# coolrunner_bob.net
KiCad netlist of a schematic drawn in EAGLE
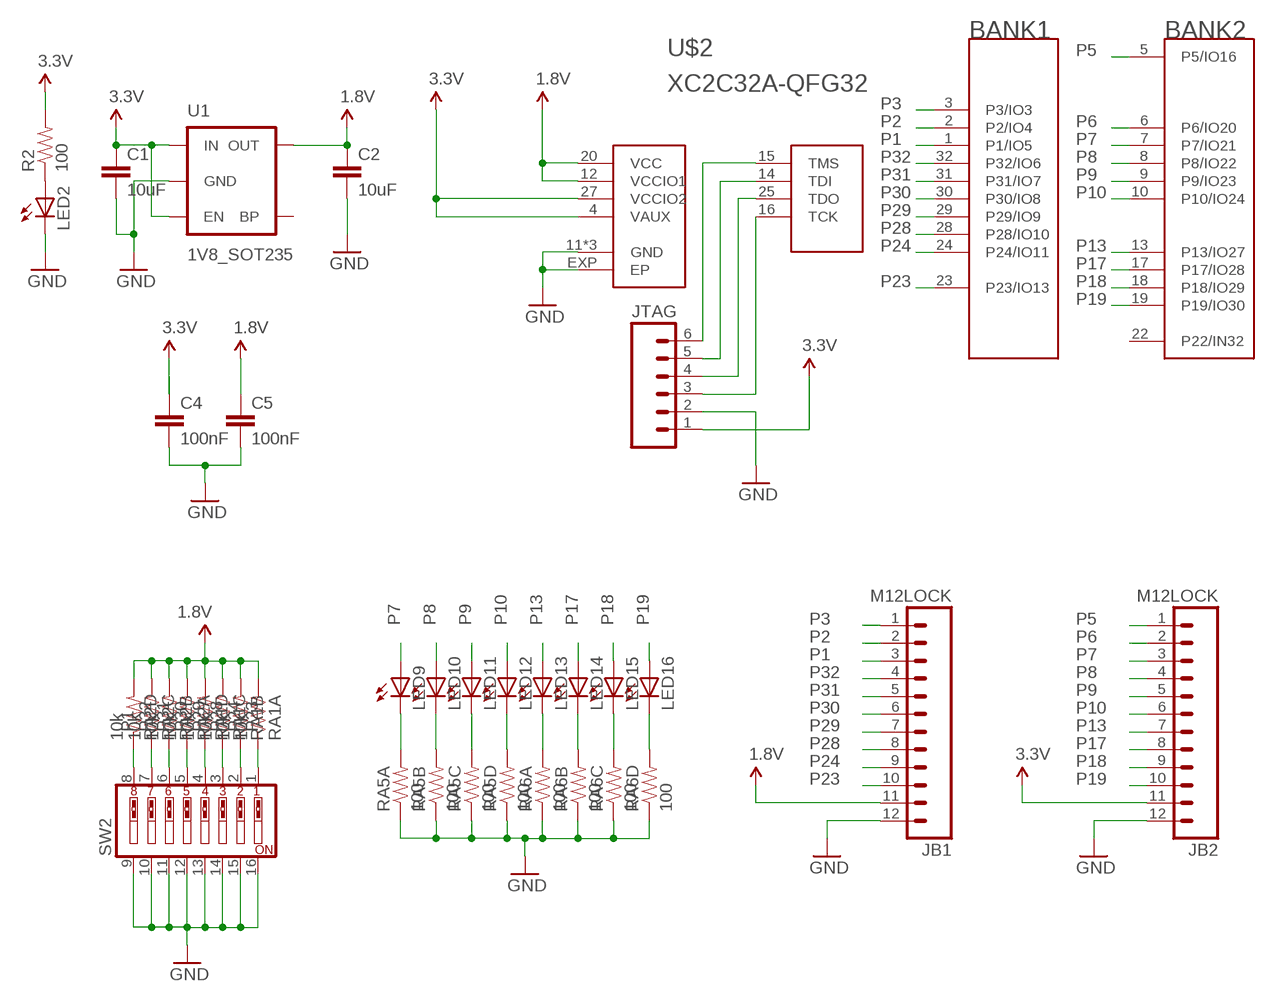
[diagram p0: schematic, sheet 1]

(export (version "E")
  (design (tool "Eeschema 10.0.6"))
  (components
    (comp (ref "C1")
      (value "10uF")
      (footprint "eagle-import:0805")
      (libsource (lib "eagle-import") (part "CAP0805"))
    )
    (comp (ref "C2")
      (value "10uF")
      (footprint "eagle-import:0805")
      (libsource (lib "eagle-import") (part "CAP0805"))
    )
    (comp (ref "C4")
      (value "100nF")
      (footprint "eagle-import:0402-CAP")
      (libsource (lib "eagle-import") (part "CAP0402-CAP"))
    )
    (comp (ref "C5")
      (value "100nF")
      (footprint "eagle-import:0402-CAP")
      (libsource (lib "eagle-import") (part "CAP0402-CAP"))
    )
    (comp (ref "JB1")
      (value "M12LOCK")
      (footprint "eagle-import:1X12_LOCK")
      (libsource (lib "eagle-import") (part "M12LOCK"))
    )
    (comp (ref "JB2")
      (value "M12LOCK")
      (footprint "eagle-import:1X12_LOCK")
      (libsource (lib "eagle-import") (part "M12LOCK"))
    )
    (comp (ref "JTAG")
      (value "M06LOCK")
      (footprint "eagle-import:1X06_LOCK")
      (libsource (lib "eagle-import") (part "M06LOCK"))
    )
    (comp (ref "LED2")
      (value "LED0603")
      (footprint "eagle-import:LED-0603")
      (libsource (lib "eagle-import") (part "LED0603"))
    )
    (comp (ref "LED9")
      (value "LED0603")
      (footprint "eagle-import:LED-0603")
      (libsource (lib "eagle-import") (part "LED0603"))
    )
    (comp (ref "LED10")
      (value "LED0603")
      (footprint "eagle-import:LED-0603")
      (libsource (lib "eagle-import") (part "LED0603"))
    )
    (comp (ref "LED11")
      (value "LED0603")
      (footprint "eagle-import:LED-0603")
      (libsource (lib "eagle-import") (part "LED0603"))
    )
    (comp (ref "LED12")
      (value "LED0603")
      (footprint "eagle-import:LED-0603")
      (libsource (lib "eagle-import") (part "LED0603"))
    )
    (comp (ref "LED13")
      (value "LED0603")
      (footprint "eagle-import:LED-0603")
      (libsource (lib "eagle-import") (part "LED0603"))
    )
    (comp (ref "LED14")
      (value "LED0603")
      (footprint "eagle-import:LED-0603")
      (libsource (lib "eagle-import") (part "LED0603"))
    )
    (comp (ref "LED15")
      (value "LED0603")
      (footprint "eagle-import:LED-0603")
      (libsource (lib "eagle-import") (part "LED0603"))
    )
    (comp (ref "LED16")
      (value "LED0603")
      (footprint "eagle-import:LED-0603")
      (libsource (lib "eagle-import") (part "LED0603"))
    )
    (comp (ref "R2")
      (value "100")
      (footprint "eagle-import:0603-RES")
      (libsource (lib "eagle-import") (part "RESISTOR0603-RES"))
    )
    (comp (ref "RA1")
      (value "10k")
      (footprint "eagle-import:0603-ARV")
      (libsource (lib "eagle-import") (part "RESISTOR_ARRAY0603_X4"))
    )
    (comp (ref "RA2")
      (value "10k")
      (footprint "eagle-import:0603-ARV")
      (libsource (lib "eagle-import") (part "RESISTOR_ARRAY0603_X4"))
    )
    (comp (ref "RA5")
      (value "100")
      (footprint "eagle-import:0603-ARV")
      (libsource (lib "eagle-import") (part "RESISTOR_ARRAY0603_X4"))
    )
    (comp (ref "RA6")
      (value "100")
      (footprint "eagle-import:0603-ARV")
      (libsource (lib "eagle-import") (part "RESISTOR_ARRAY0603_X4"))
    )
    (comp (ref "SW2")
      (value "SW_DIP-8")
      (footprint "eagle-import:DIPSWITCH-08")
      (libsource (lib "eagle-import") (part "SW_DIP-8"))
    )
    (comp (ref "U$2")
      (value "XC2C32A-QFG32")
      (footprint "eagle-import:QFN32-5X5")
      (libsource (lib "eagle-import") (part "XC2C32A-QFG32"))
    )
    (comp (ref "U1")
      (value "1V8_SOT235")
      (footprint "eagle-import:SOT23-5")
      (libsource (lib "eagle-import") (part "V_REG_LDOSMD"))
    )
  )
  (nets
    (net (code "1") (name "/P1") (class "Default")
      (node (ref "JB1") (pin "3") (pinfunction "3_3") (pintype "passive"))
      (node (ref "RA2") (pin "4") (pinfunction "1_4") (pintype "passive"))
      (node (ref "SW2") (pin "8") (pinfunction "8_8") (pintype "passive"))
      (node (ref "U$2") (pin "1") (pinfunction "P1/IO5_1") (pintype "bidirectional"))
    )
    (net (code "2") (name "/P2") (class "Default")
      (node (ref "JB1") (pin "2") (pinfunction "2_2") (pintype "passive"))
      (node (ref "U$2") (pin "2") (pinfunction "P2/IO4_2") (pintype "bidirectional"))
    )
    (net (code "3") (name "/P3") (class "Default")
      (node (ref "JB1") (pin "1") (pinfunction "1_1") (pintype "passive"))
      (node (ref "U$2") (pin "3") (pinfunction "P3/IO3_3") (pintype "bidirectional"))
    )
    (net (code "4") (name "/P5") (class "Default")
      (node (ref "JB2") (pin "1") (pinfunction "1_1") (pintype "passive"))
      (node (ref "U$2") (pin "5") (pinfunction "P5/IO16_5") (pintype "bidirectional"))
    )
    (net (code "5") (name "/P6") (class "Default")
      (node (ref "JB2") (pin "2") (pinfunction "2_2") (pintype "passive"))
      (node (ref "U$2") (pin "6") (pinfunction "P6/IO20_6") (pintype "bidirectional"))
    )
    (net (code "6") (name "/P7") (class "Default")
      (node (ref "JB2") (pin "3") (pinfunction "3_3") (pintype "passive"))
      (node (ref "LED9") (pin "A") (pinfunction "A_A") (pintype "passive"))
      (node (ref "U$2") (pin "7") (pinfunction "P7/IO21_7") (pintype "bidirectional"))
    )
    (net (code "7") (name "/P8") (class "Default")
      (node (ref "JB2") (pin "4") (pinfunction "4_4") (pintype "passive"))
      (node (ref "LED10") (pin "A") (pinfunction "A_A") (pintype "passive"))
      (node (ref "U$2") (pin "8") (pinfunction "P8/IO22_8") (pintype "bidirectional"))
    )
    (net (code "8") (name "/P9") (class "Default")
      (node (ref "JB2") (pin "5") (pinfunction "5_5") (pintype "passive"))
      (node (ref "LED11") (pin "A") (pinfunction "A_A") (pintype "passive"))
      (node (ref "U$2") (pin "9") (pinfunction "P9/IO23_9") (pintype "bidirectional"))
    )
    (net (code "9") (name "/P10") (class "Default")
      (node (ref "JB2") (pin "6") (pinfunction "6_6") (pintype "passive"))
      (node (ref "LED12") (pin "A") (pinfunction "A_A") (pintype "passive"))
      (node (ref "U$2") (pin "10") (pinfunction "P10/IO24_10") (pintype "bidirectional"))
    )
    (net (code "10") (name "/P13") (class "Default")
      (node (ref "JB2") (pin "7") (pinfunction "7_7") (pintype "passive"))
      (node (ref "LED13") (pin "A") (pinfunction "A_A") (pintype "passive"))
      (node (ref "U$2") (pin "13") (pinfunction "P13/IO27_13") (pintype "bidirectional"))
    )
    (net (code "11") (name "/P17") (class "Default")
      (node (ref "JB2") (pin "8") (pinfunction "8_8") (pintype "passive"))
      (node (ref "LED14") (pin "A") (pinfunction "A_A") (pintype "passive"))
      (node (ref "U$2") (pin "17") (pinfunction "P17/IO28_17") (pintype "bidirectional"))
    )
    (net (code "12") (name "/P18") (class "Default")
      (node (ref "JB2") (pin "9") (pinfunction "9_9") (pintype "passive"))
      (node (ref "LED15") (pin "A") (pinfunction "A_A") (pintype "passive"))
      (node (ref "U$2") (pin "18") (pinfunction "P18/IO29_18") (pintype "bidirectional"))
    )
    (net (code "13") (name "/P19") (class "Default")
      (node (ref "JB2") (pin "10") (pinfunction "10_10") (pintype "passive"))
      (node (ref "LED16") (pin "A") (pinfunction "A_A") (pintype "passive"))
      (node (ref "U$2") (pin "19") (pinfunction "P19/IO30_19") (pintype "bidirectional"))
    )
    (net (code "14") (name "/P23") (class "Default")
      (node (ref "JB1") (pin "10") (pinfunction "10_10") (pintype "passive"))
      (node (ref "RA1") (pin "1") (pinfunction "1_1") (pintype "passive"))
      (node (ref "SW2") (pin "1") (pinfunction "1_1") (pintype "passive"))
      (node (ref "U$2") (pin "23") (pinfunction "P23/IO13_23") (pintype "bidirectional"))
    )
    (net (code "15") (name "/P24") (class "Default")
      (node (ref "JB1") (pin "9") (pinfunction "9_9") (pintype "passive"))
      (node (ref "RA1") (pin "2") (pinfunction "1_2") (pintype "passive"))
      (node (ref "SW2") (pin "2") (pinfunction "2_2") (pintype "passive"))
      (node (ref "U$2") (pin "24") (pinfunction "P24/IO11_24") (pintype "bidirectional"))
    )
    (net (code "16") (name "/P28") (class "Default")
      (node (ref "JB1") (pin "8") (pinfunction "8_8") (pintype "passive"))
      (node (ref "RA1") (pin "3") (pinfunction "1_3") (pintype "passive"))
      (node (ref "SW2") (pin "3") (pinfunction "3_3") (pintype "passive"))
      (node (ref "U$2") (pin "28") (pinfunction "P28/IO10_28") (pintype "bidirectional"))
    )
    (net (code "17") (name "/P29") (class "Default")
      (node (ref "JB1") (pin "7") (pinfunction "7_7") (pintype "passive"))
      (node (ref "RA1") (pin "4") (pinfunction "1_4") (pintype "passive"))
      (node (ref "SW2") (pin "4") (pinfunction "4_4") (pintype "passive"))
      (node (ref "U$2") (pin "29") (pinfunction "P29/IO9_29") (pintype "bidirectional"))
    )
    (net (code "18") (name "/P30") (class "Default")
      (node (ref "JB1") (pin "6") (pinfunction "6_6") (pintype "passive"))
      (node (ref "RA2") (pin "1") (pinfunction "1_1") (pintype "passive"))
      (node (ref "SW2") (pin "5") (pinfunction "5_5") (pintype "passive"))
      (node (ref "U$2") (pin "30") (pinfunction "P30/IO8_30") (pintype "bidirectional"))
    )
    (net (code "19") (name "/P31") (class "Default")
      (node (ref "JB1") (pin "5") (pinfunction "5_5") (pintype "passive"))
      (node (ref "RA2") (pin "2") (pinfunction "1_2") (pintype "passive"))
      (node (ref "SW2") (pin "6") (pinfunction "6_6") (pintype "passive"))
      (node (ref "U$2") (pin "31") (pinfunction "P31/IO7_31") (pintype "bidirectional"))
    )
    (net (code "20") (name "/P32") (class "Default")
      (node (ref "JB1") (pin "4") (pinfunction "4_4") (pintype "passive"))
      (node (ref "RA2") (pin "3") (pinfunction "1_3") (pintype "passive"))
      (node (ref "SW2") (pin "7") (pinfunction "7_7") (pintype "passive"))
      (node (ref "U$2") (pin "32") (pinfunction "P32/IO6_32") (pintype "bidirectional"))
    )
    (net (code "21") (name "1.8V") (class "Default")
      (node (ref "C2") (pin "1") (pinfunction "1_1") (pintype "passive"))
      (node (ref "C5") (pin "1") (pinfunction "1_1") (pintype "passive"))
      (node (ref "JB1") (pin "11") (pinfunction "11_11") (pintype "passive"))
      (node (ref "RA1") (pin "5") (pinfunction "2_5") (pintype "passive"))
      (node (ref "RA1") (pin "6") (pinfunction "2_6") (pintype "passive"))
      (node (ref "RA1") (pin "7") (pinfunction "2_7") (pintype "passive"))
      (node (ref "RA1") (pin "8") (pinfunction "2_8") (pintype "passive"))
      (node (ref "RA2") (pin "5") (pinfunction "2_5") (pintype "passive"))
      (node (ref "RA2") (pin "6") (pinfunction "2_6") (pintype "passive"))
      (node (ref "RA2") (pin "7") (pinfunction "2_7") (pintype "passive"))
      (node (ref "RA2") (pin "8") (pinfunction "2_8") (pintype "passive"))
      (node (ref "U$2") (pin "12") (pinfunction "VCCIO1_12") (pintype "bidirectional"))
      (node (ref "U$2") (pin "20") (pinfunction "VCC_20") (pintype "bidirectional"))
      (node (ref "U1") (pin "5") (pinfunction "OUT_5") (pintype "passive"))
    )
    (net (code "22") (name "3.3V") (class "Default")
      (node (ref "C1") (pin "1") (pinfunction "1_1") (pintype "passive"))
      (node (ref "C4") (pin "1") (pinfunction "1_1") (pintype "passive"))
      (node (ref "JB2") (pin "11") (pinfunction "11_11") (pintype "passive"))
      (node (ref "JTAG") (pin "1") (pinfunction "1_1") (pintype "passive"))
      (node (ref "R2") (pin "2") (pinfunction "2_2") (pintype "passive"))
      (node (ref "U$2") (pin "27") (pinfunction "VCCIO2_27") (pintype "bidirectional"))
      (node (ref "U$2") (pin "4") (pinfunction "VAUX_4") (pintype "bidirectional"))
      (node (ref "U1") (pin "1") (pinfunction "IN_1") (pintype "input"))
      (node (ref "U1") (pin "3") (pinfunction "EN_3") (pintype "input"))
    )
    (net (code "23") (name "GND") (class "Default")
      (node (ref "C1") (pin "2") (pinfunction "2_2") (pintype "passive"))
      (node (ref "C2") (pin "2") (pinfunction "2_2") (pintype "passive"))
      (node (ref "C4") (pin "2") (pinfunction "2_2") (pintype "passive"))
      (node (ref "C5") (pin "2") (pinfunction "2_2") (pintype "passive"))
      (node (ref "JB1") (pin "12") (pinfunction "12_12") (pintype "passive"))
      (node (ref "JB2") (pin "12") (pinfunction "12_12") (pintype "passive"))
      (node (ref "JTAG") (pin "2") (pinfunction "2_2") (pintype "passive"))
      (node (ref "LED2") (pin "C") (pinfunction "C_C") (pintype "passive"))
      (node (ref "RA5") (pin "1") (pinfunction "1_1") (pintype "passive"))
      (node (ref "RA5") (pin "2") (pinfunction "1_2") (pintype "passive"))
      (node (ref "RA5") (pin "3") (pinfunction "1_3") (pintype "passive"))
      (node (ref "RA5") (pin "4") (pinfunction "1_4") (pintype "passive"))
      (node (ref "RA6") (pin "1") (pinfunction "1_1") (pintype "passive"))
      (node (ref "RA6") (pin "2") (pinfunction "1_2") (pintype "passive"))
      (node (ref "RA6") (pin "3") (pinfunction "1_3") (pintype "passive"))
      (node (ref "RA6") (pin "4") (pinfunction "1_4") (pintype "passive"))
      (node (ref "SW2") (pin "10") (pinfunction "10_10") (pintype "passive"))
      (node (ref "SW2") (pin "11") (pinfunction "11_11") (pintype "passive"))
      (node (ref "SW2") (pin "12") (pinfunction "12_12") (pintype "passive"))
      (node (ref "SW2") (pin "13") (pinfunction "13_13") (pintype "passive"))
      (node (ref "SW2") (pin "14") (pinfunction "14_14") (pintype "passive"))
      (node (ref "SW2") (pin "15") (pinfunction "15_15") (pintype "passive"))
      (node (ref "SW2") (pin "16") (pinfunction "16_16") (pintype "passive"))
      (node (ref "SW2") (pin "9") (pinfunction "9_9") (pintype "passive"))
      (node (ref "U$2") (pin "11") (pinfunction "GND_11") (pintype "bidirectional"))
      (node (ref "U$2") (pin "21") (pinfunction "GND_21") (pintype "bidirectional"))
      (node (ref "U$2") (pin "26") (pinfunction "GND_26") (pintype "bidirectional"))
      (node (ref "U$2") (pin "EXP") (pinfunction "EP_EXP") (pintype "bidirectional"))
      (node (ref "U1") (pin "2") (pinfunction "GND_2") (pintype "input"))
    )
    (net (code "24") (name "Net-(LED2-PadA)") (class "Default")
      (node (ref "LED2") (pin "A") (pinfunction "A_A") (pintype "passive"))
      (node (ref "R2") (pin "1") (pinfunction "1_1") (pintype "passive"))
    )
    (net (code "25") (name "Net-(RA5A-2)") (class "Default")
      (node (ref "LED9") (pin "C") (pinfunction "C_C") (pintype "passive"))
      (node (ref "RA5") (pin "8") (pinfunction "2_8") (pintype "passive"))
    )
    (net (code "26") (name "Net-(RA5B-2)") (class "Default")
      (node (ref "LED10") (pin "C") (pinfunction "C_C") (pintype "passive"))
      (node (ref "RA5") (pin "7") (pinfunction "2_7") (pintype "passive"))
    )
    (net (code "27") (name "Net-(RA5C-2)") (class "Default")
      (node (ref "LED11") (pin "C") (pinfunction "C_C") (pintype "passive"))
      (node (ref "RA5") (pin "6") (pinfunction "2_6") (pintype "passive"))
    )
    (net (code "28") (name "Net-(RA5D-2)") (class "Default")
      (node (ref "LED12") (pin "C") (pinfunction "C_C") (pintype "passive"))
      (node (ref "RA5") (pin "5") (pinfunction "2_5") (pintype "passive"))
    )
    (net (code "29") (name "Net-(RA6A-2)") (class "Default")
      (node (ref "LED13") (pin "C") (pinfunction "C_C") (pintype "passive"))
      (node (ref "RA6") (pin "8") (pinfunction "2_8") (pintype "passive"))
    )
    (net (code "30") (name "Net-(RA6B-2)") (class "Default")
      (node (ref "LED14") (pin "C") (pinfunction "C_C") (pintype "passive"))
      (node (ref "RA6") (pin "7") (pinfunction "2_7") (pintype "passive"))
    )
    (net (code "31") (name "Net-(RA6C-2)") (class "Default")
      (node (ref "LED15") (pin "C") (pinfunction "C_C") (pintype "passive"))
      (node (ref "RA6") (pin "6") (pinfunction "2_6") (pintype "passive"))
    )
    (net (code "32") (name "Net-(RA6D-2)") (class "Default")
      (node (ref "LED16") (pin "C") (pinfunction "C_C") (pintype "passive"))
      (node (ref "RA6") (pin "5") (pinfunction "2_5") (pintype "passive"))
    )
    (net (code "33") (name "Net-(U$2-TCK)") (class "Default")
      (node (ref "JTAG") (pin "3") (pinfunction "3_3") (pintype "passive"))
      (node (ref "U$2") (pin "16") (pinfunction "TCK_16") (pintype "bidirectional"))
    )
    (net (code "34") (name "Net-(U$2-TDI)") (class "Default")
      (node (ref "JTAG") (pin "5") (pinfunction "5_5") (pintype "passive"))
      (node (ref "U$2") (pin "14") (pinfunction "TDI_14") (pintype "bidirectional"))
    )
    (net (code "35") (name "Net-(U$2-TDO)") (class "Default")
      (node (ref "JTAG") (pin "4") (pinfunction "4_4") (pintype "passive"))
      (node (ref "U$2") (pin "25") (pinfunction "TDO_25") (pintype "bidirectional"))
    )
    (net (code "36") (name "Net-(U$2-TMS)") (class "Default")
      (node (ref "JTAG") (pin "6") (pinfunction "6_6") (pintype "passive"))
      (node (ref "U$2") (pin "15") (pinfunction "TMS_15") (pintype "bidirectional"))
    )
    (net (code "37") (name "unconnected-(U$2-P22{slash}IN32-Pad22)") (class "Default")
      (node (ref "U$2") (pin "22") (pinfunction "P22/IN32_22") (pintype "bidirectional"))
    )
    (net (code "38") (name "unconnected-(U1-BP-Pad4)") (class "Default")
      (node (ref "U1") (pin "4") (pinfunction "BP_4") (pintype "input"))
    )
  )
)
